# TEMP_MGT.net
KiCad netlist of a schematic drawn in Altium Designer
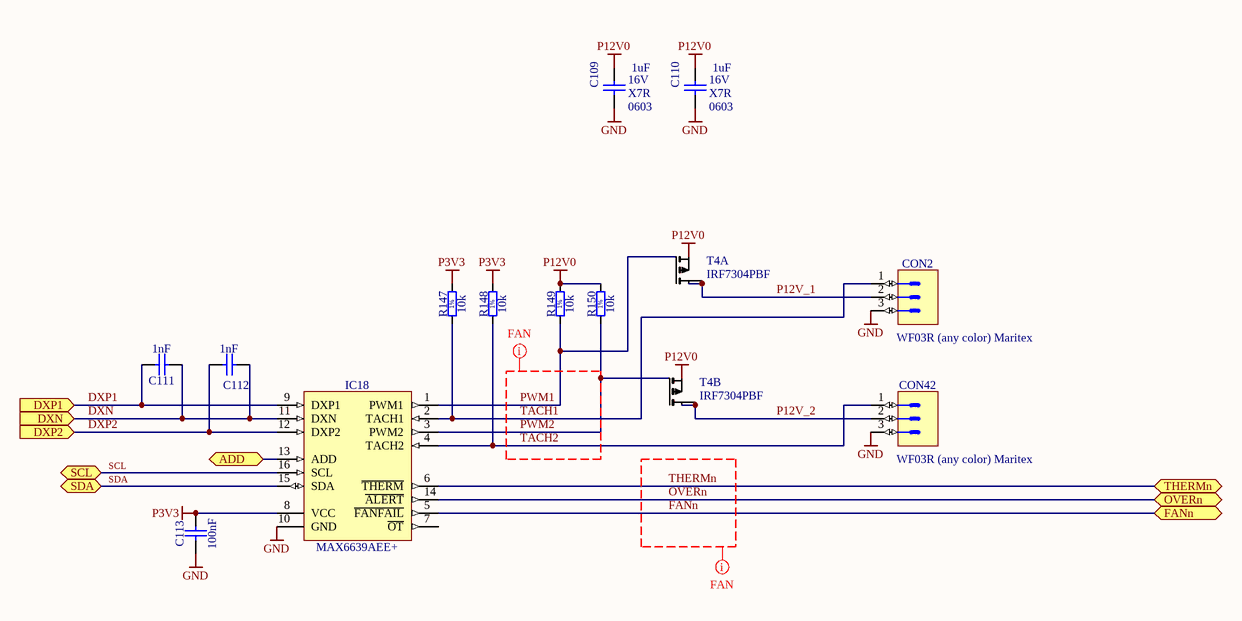
[diagram p0: TEMP_MGT.SchDoc]

(export (version "E")
  (design (tool "Eeschema 10.0.6"))
  (components
    (comp (ref "C109")
      (value "1uF")
      (footprint "CAPC1608X87N")
      (description "Non-polarised capacitor")
      (fields
        (field (name "PART NUMBER") "CC0603_1UF_16V_10%_X7R")
        (field (name "VOLTAGE") "16V")
        (field (name "TC") "X7R")
        (field (name "TOLERANCE") "±10%")
        (field (name "CASE") "0603")
        (field (name "AUTHOR") "CERN DEM JLC")
      )
      (libsource (lib "Capacitors") (part "Capacitor - non polarized"))
    )
    (comp (ref "C110")
      (value "1uF")
      (footprint "CAPC1608X87N")
      (description "Non-polarised capacitor")
      (fields
        (field (name "PART NUMBER") "CC0603_1UF_16V_10%_X7R")
        (field (name "VOLTAGE") "16V")
        (field (name "TC") "X7R")
        (field (name "TOLERANCE") "±10%")
        (field (name "CASE") "0603")
        (field (name "AUTHOR") "CERN DEM JLC")
      )
      (libsource (lib "Capacitors") (part "Capacitor - non polarized"))
    )
    (comp (ref "C111")
      (value "1nF")
      (footprint "CAPC1608X87N")
      (description "Non-polarised capacitor")
      (fields
        (field (name "PART NUMBER") "CC0603_1NF_50V_10%_X7R")
        (field (name "VOLTAGE") "50V")
        (field (name "AUTHOR") "CERN DEM JLC")
      )
      (libsource (lib "Capacitors") (part "Capacitor - non polarized"))
    )
    (comp (ref "C112")
      (value "1nF")
      (footprint "CAPC1608X87N")
      (description "Non-polarised capacitor")
      (fields
        (field (name "PART NUMBER") "CC0603_1NF_50V_10%_X7R")
        (field (name "VOLTAGE") "50V")
        (field (name "AUTHOR") "CERN DEM JLC")
      )
      (libsource (lib "Capacitors") (part "Capacitor - non polarized"))
    )
    (comp (ref "C113")
      (value "100nF")
      (footprint "CAPC0603X33N")
      (description "Non-polarised capacitor")
      (fields
        (field (name "PART NUMBER") "CC0201_100NF_6.3V_10%_X5R")
        (field (name "VOLTAGE") "6.3V")
        (field (name "AUTHOR") "CERN DEM JLC")
      )
      (libsource (lib "Capacitors") (part "Capacitor - non polarized"))
    )
    (comp (ref "CON2")
      (value "WF03R (any color) Maritex")
      (footprint "MOLEX_22-05-7038")
      (description "Connector 3 Male")
      (fields
        (field (name "PART NUMBER") "MOLEX_22-05-7038")
        (field (name "MANUFACTURER") "MOLEX")
        (field (name "AUTHOR") "CERN DEM JLC")
      )
      (libsource (lib "Connectors") (part "Connector 3 Male"))
    )
    (comp (ref "CON42")
      (value "WF03R (any color) Maritex")
      (footprint "MOLEX_22-05-7038")
      (description "Connector 3 Male")
      (fields
        (field (name "PART NUMBER") "MOLEX_22-05-7038")
        (field (name "MANUFACTURER") "MOLEX")
        (field (name "AUTHOR") "CERN DEM JLC")
      )
      (libsource (lib "Connectors") (part "Connector 3 Male"))
    )
    (comp (ref "IC18")
      (value "MAX6639AEE+")
      (footprint "SOP63P600X175-16N")
      (description "2-Channel Temperature Monitor with Dual, Automatic, PWM Fan-Speed Controller")
      (fields (field (name "MANUFACTURER") "MAXIM") (field (name "AUTHOR") "CERN DEM JLC"))
      (libsource (lib "ICs And Semiconductors") (part "MAX6639AEE+"))
    )
    (comp (ref "R147")
      (value "10k")
      (footprint "RESC1005X40N")
      (description "Resistor - 1%")
      (fields
        (field (name "PART NUMBER") "R0402_10K_1%_0.0625W_100PPM")
        (field (name "POWER") "0.0625W")
        (field (name "AUTHOR") "CERN DEM JLC")
      )
      (libsource (lib "Resistors") (part "Resistor - 1%"))
    )
    (comp (ref "R148")
      (value "10k")
      (footprint "RESC1005X40N")
      (description "Resistor - 1%")
      (fields
        (field (name "PART NUMBER") "R0402_10K_1%_0.0625W_100PPM")
        (field (name "POWER") "0.0625W")
        (field (name "AUTHOR") "CERN DEM JLC")
      )
      (libsource (lib "Resistors") (part "Resistor - 1%"))
    )
    (comp (ref "R149")
      (value "10k")
      (footprint "RESC1005X40N")
      (description "Resistor - 1%")
      (fields
        (field (name "PART NUMBER") "R0402_10K_1%_0.0625W_100PPM")
        (field (name "POWER") "0.0625W")
        (field (name "AUTHOR") "CERN DEM JLC")
      )
      (libsource (lib "Resistors") (part "Resistor - 1%"))
    )
    (comp (ref "R150")
      (value "10k")
      (footprint "RESC1005X40N")
      (description "Resistor - 1%")
      (fields
        (field (name "PART NUMBER") "R0402_10K_1%_0.0625W_100PPM")
        (field (name "POWER") "0.0625W")
        (field (name "AUTHOR") "CERN DEM JLC")
      )
      (libsource (lib "Resistors") (part "Resistor - 1%"))
    )
    (comp (ref "T4")
      (value "IRF7304PBF")
      (footprint "so-8")
      (description "dual PMOS   20V 4,3A 2,0W 0,09R")
      (libsource (lib "LIBRARY_SCH") (part "Q_IRF7304"))
    )
  )
  (nets
    (net (code "1") (name "/ADD") (class "Default")
      (node (ref "IC18") (pin "13") (pinfunction "ADD_13") (pintype "input"))
    )
    (net (code "2") (name "/DXN") (class "Default")
      (node (ref "C111") (pin "1") (pinfunction "1_1") (pintype "passive"))
      (node (ref "C112") (pin "1") (pinfunction "1_1") (pintype "passive"))
      (node (ref "IC18") (pin "11") (pinfunction "DXN_11") (pintype "input"))
    )
    (net (code "3") (name "/DXP1") (class "Default")
      (node (ref "C111") (pin "2") (pinfunction "2_2") (pintype "passive"))
      (node (ref "IC18") (pin "9") (pinfunction "DXP1_9") (pintype "input"))
    )
    (net (code "4") (name "/DXP2") (class "Default")
      (node (ref "C112") (pin "2") (pinfunction "2_2") (pintype "passive"))
      (node (ref "IC18") (pin "12") (pinfunction "DXP2_12") (pintype "input"))
    )
    (net (code "5") (name "/FANn") (class "Default")
      (node (ref "IC18") (pin "5") (pinfunction "~{FANFAIL}_5") (pintype "output"))
    )
    (net (code "6") (name "/OVERn") (class "Default")
      (node (ref "IC18") (pin "14") (pinfunction "~{ALERT}_14") (pintype "output"))
    )
    (net (code "7") (name "/P12V_1") (class "Default")
      (node (ref "CON2") (pin "2") (pinfunction "2_2") (pintype "bidirectional"))
      (node (ref "T4") (pin "7") (pinfunction "D1_7") (pintype "passive"))
      (node (ref "T4") (pin "8") (pinfunction "D1_8") (pintype "passive"))
    )
    (net (code "8") (name "/P12V_2") (class "Default")
      (node (ref "CON42") (pin "2") (pinfunction "2_2") (pintype "bidirectional"))
      (node (ref "T4") (pin "5") (pinfunction "D2_5") (pintype "passive"))
      (node (ref "T4") (pin "6") (pinfunction "D2_6") (pintype "passive"))
    )
    (net (code "9") (name "/PWM1") (class "Default")
      (node (ref "IC18") (pin "1") (pinfunction "PWM1_1") (pintype "output"))
      (node (ref "R149") (pin "1") (pinfunction "1_1") (pintype "passive"))
      (node (ref "T4") (pin "2") (pinfunction "G1_2") (pintype "input"))
    )
    (net (code "10") (name "/PWM2") (class "Default")
      (node (ref "IC18") (pin "3") (pinfunction "PWM2_3") (pintype "output"))
      (node (ref "R150") (pin "1") (pinfunction "1_1") (pintype "passive"))
      (node (ref "T4") (pin "4") (pinfunction "G2_4") (pintype "input"))
    )
    (net (code "11") (name "/SCL") (class "Default")
      (node (ref "IC18") (pin "16") (pinfunction "SCL_16") (pintype "input"))
    )
    (net (code "12") (name "/SDA") (class "Default")
      (node (ref "IC18") (pin "15") (pinfunction "SDA_15") (pintype "bidirectional"))
    )
    (net (code "13") (name "/TACH1") (class "Default")
      (node (ref "CON2") (pin "1") (pinfunction "1_1") (pintype "bidirectional"))
      (node (ref "IC18") (pin "2") (pinfunction "TACH1_2") (pintype "input"))
      (node (ref "R147") (pin "1") (pinfunction "1_1") (pintype "passive"))
    )
    (net (code "14") (name "/TACH2") (class "Default")
      (node (ref "CON42") (pin "1") (pinfunction "1_1") (pintype "bidirectional"))
      (node (ref "IC18") (pin "4") (pinfunction "TACH2_4") (pintype "input"))
      (node (ref "R148") (pin "1") (pinfunction "1_1") (pintype "passive"))
    )
    (net (code "15") (name "/THERMn") (class "Default")
      (node (ref "IC18") (pin "6") (pinfunction "~{THERM}_6") (pintype "output"))
    )
    (net (code "16") (name "GND") (class "Default")
      (node (ref "C109") (pin "1") (pinfunction "1_1") (pintype "passive"))
      (node (ref "C110") (pin "1") (pinfunction "1_1") (pintype "passive"))
      (node (ref "C113") (pin "1") (pinfunction "1_1") (pintype "passive"))
      (node (ref "CON2") (pin "3") (pinfunction "3_3") (pintype "bidirectional"))
      (node (ref "CON42") (pin "3") (pinfunction "3_3") (pintype "bidirectional"))
      (node (ref "IC18") (pin "10") (pinfunction "GND_10") (pintype "power_in"))
    )
    (net (code "17") (name "P3V3") (class "Default")
      (node (ref "C113") (pin "2") (pinfunction "2_2") (pintype "passive"))
      (node (ref "IC18") (pin "8") (pinfunction "VCC_8") (pintype "power_in"))
      (node (ref "R147") (pin "2") (pinfunction "2_2") (pintype "passive"))
      (node (ref "R148") (pin "2") (pinfunction "2_2") (pintype "passive"))
    )
    (net (code "18") (name "P12V0") (class "Default")
      (node (ref "C109") (pin "2") (pinfunction "2_2") (pintype "passive"))
      (node (ref "C110") (pin "2") (pinfunction "2_2") (pintype "passive"))
      (node (ref "R149") (pin "2") (pinfunction "2_2") (pintype "passive"))
      (node (ref "R150") (pin "2") (pinfunction "2_2") (pintype "passive"))
      (node (ref "T4") (pin "1") (pinfunction "S1_1") (pintype "passive"))
      (node (ref "T4") (pin "3") (pinfunction "S2_3") (pintype "passive"))
    )
    (net (code "19") (name "unconnected-(IC18-~{OT}-Pad7)") (class "Default")
      (node (ref "IC18") (pin "7") (pinfunction "~{OT}_7") (pintype "output"))
    )
  )
)
